# IDC_HD68_Adapter.net
KiCad netlist of a schematic drawn in Altium Designer
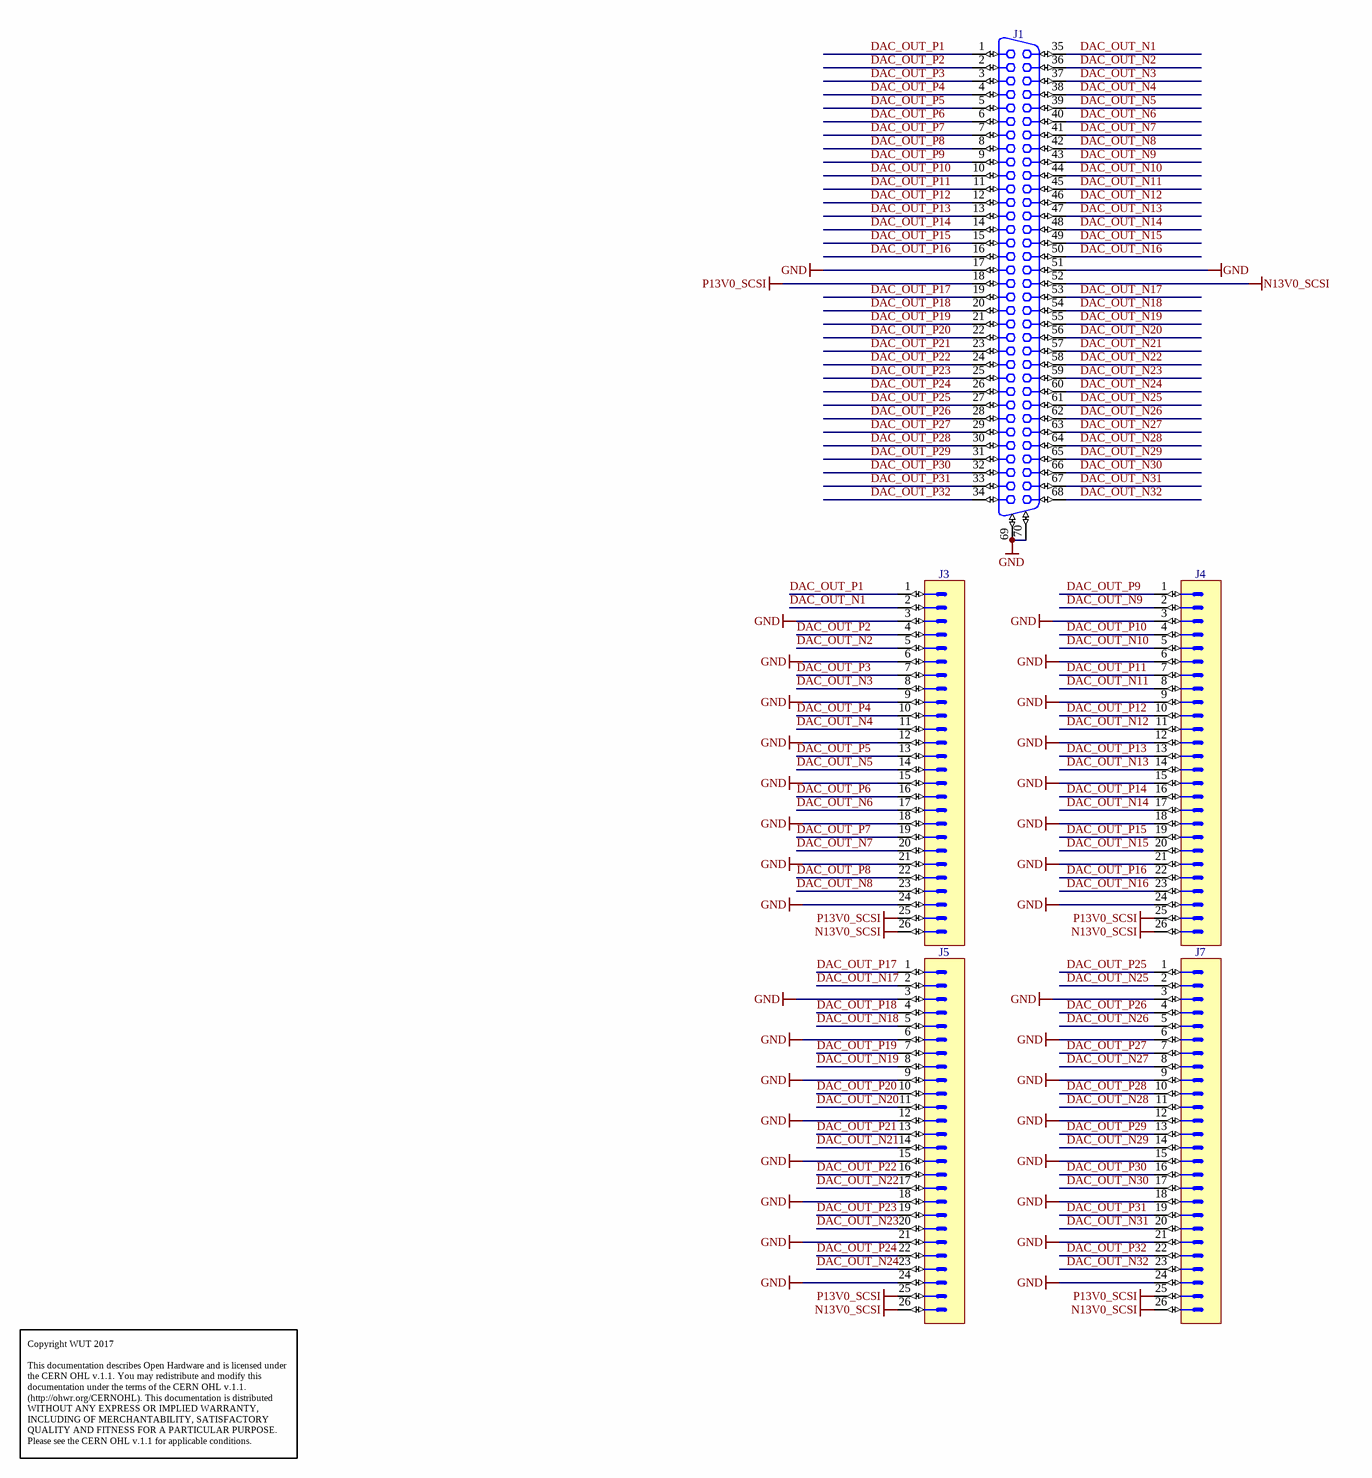
[diagram p0: IDC_HD68_Adapter.SchDoc]

(export (version "E")
  (design (tool "Eeschema 10.0.6"))
  (components
    (comp (ref "J1")
      (value "D-SUB")
      (footprint "TYCO_5787082-7")
      (description "68 contacts, AMPLIMITE .050\", Right Angled Receptacle Series III")
      (fields
        (field (name "PART NUMBER") "TYCO_5787082-7")
        (field (name "MANUFACTURER") "TYCO ELECTRONICS")
        (field (name "AUTHOR") "CERN DEM JLC")
      )
      (libsource (lib "Connectors") (part "TYCO_5787082-7"))
    )
    (comp (ref "J3")
      (value "Header 26")
      (footprint "3M_N2526-6002RB")
      (description "Connector 26 Male")
      (fields
        (field (name "PART NUMBER") "3M_N2526-6002RB")
        (field (name "MANUFACTURER") "3M")
        (field (name "AUTHOR") "CERN DEM JLC")
      )
      (libsource (lib "Connectors") (part "Connector 26 Male"))
    )
    (comp (ref "J4")
      (value "Header 26")
      (footprint "3M_N2526-6002RB")
      (description "Connector 26 Male")
      (fields
        (field (name "PART NUMBER") "3M_N2526-6002RB")
        (field (name "MANUFACTURER") "3M")
        (field (name "AUTHOR") "CERN DEM JLC")
      )
      (libsource (lib "Connectors") (part "Connector 26 Male"))
    )
    (comp (ref "J5")
      (value "Header 26")
      (footprint "3M_N2526-6002RB")
      (description "Connector 26 Male")
      (fields
        (field (name "PART NUMBER") "3M_N2526-6002RB")
        (field (name "MANUFACTURER") "3M")
        (field (name "AUTHOR") "CERN DEM JLC")
      )
      (libsource (lib "Connectors") (part "Connector 26 Male"))
    )
    (comp (ref "J7")
      (value "Header 26")
      (footprint "3M_N2526-6002RB")
      (description "Connector 26 Male")
      (fields
        (field (name "PART NUMBER") "3M_N2526-6002RB")
        (field (name "MANUFACTURER") "3M")
        (field (name "AUTHOR") "CERN DEM JLC")
      )
      (libsource (lib "Connectors") (part "Connector 26 Male"))
    )
  )
  (nets
    (net (code "1") (name "/DAC_OUT_N1") (class "Default")
      (node (ref "J1") (pin "35") (pinfunction "35_35") (pintype "bidirectional"))
      (node (ref "J3") (pin "2") (pinfunction "2_2") (pintype "bidirectional"))
    )
    (net (code "2") (name "/DAC_OUT_N2") (class "Default")
      (node (ref "J1") (pin "36") (pinfunction "36_36") (pintype "bidirectional"))
      (node (ref "J3") (pin "5") (pinfunction "5_5") (pintype "bidirectional"))
    )
    (net (code "3") (name "/DAC_OUT_N3") (class "Default")
      (node (ref "J1") (pin "37") (pinfunction "37_37") (pintype "bidirectional"))
      (node (ref "J3") (pin "8") (pinfunction "8_8") (pintype "bidirectional"))
    )
    (net (code "4") (name "/DAC_OUT_N4") (class "Default")
      (node (ref "J1") (pin "38") (pinfunction "38_38") (pintype "bidirectional"))
      (node (ref "J3") (pin "11") (pinfunction "11_11") (pintype "bidirectional"))
    )
    (net (code "5") (name "/DAC_OUT_N5") (class "Default")
      (node (ref "J1") (pin "39") (pinfunction "39_39") (pintype "bidirectional"))
      (node (ref "J3") (pin "14") (pinfunction "14_14") (pintype "bidirectional"))
    )
    (net (code "6") (name "/DAC_OUT_N6") (class "Default")
      (node (ref "J1") (pin "40") (pinfunction "40_40") (pintype "bidirectional"))
      (node (ref "J3") (pin "17") (pinfunction "17_17") (pintype "bidirectional"))
    )
    (net (code "7") (name "/DAC_OUT_N7") (class "Default")
      (node (ref "J1") (pin "41") (pinfunction "41_41") (pintype "bidirectional"))
      (node (ref "J3") (pin "20") (pinfunction "20_20") (pintype "bidirectional"))
    )
    (net (code "8") (name "/DAC_OUT_N8") (class "Default")
      (node (ref "J1") (pin "42") (pinfunction "42_42") (pintype "bidirectional"))
      (node (ref "J3") (pin "23") (pinfunction "23_23") (pintype "bidirectional"))
    )
    (net (code "9") (name "/DAC_OUT_N9") (class "Default")
      (node (ref "J1") (pin "43") (pinfunction "43_43") (pintype "bidirectional"))
      (node (ref "J4") (pin "2") (pinfunction "2_2") (pintype "bidirectional"))
    )
    (net (code "10") (name "/DAC_OUT_N10") (class "Default")
      (node (ref "J1") (pin "44") (pinfunction "44_44") (pintype "bidirectional"))
      (node (ref "J4") (pin "5") (pinfunction "5_5") (pintype "bidirectional"))
    )
    (net (code "11") (name "/DAC_OUT_N11") (class "Default")
      (node (ref "J1") (pin "45") (pinfunction "45_45") (pintype "bidirectional"))
      (node (ref "J4") (pin "8") (pinfunction "8_8") (pintype "bidirectional"))
    )
    (net (code "12") (name "/DAC_OUT_N12") (class "Default")
      (node (ref "J1") (pin "46") (pinfunction "46_46") (pintype "bidirectional"))
      (node (ref "J4") (pin "11") (pinfunction "11_11") (pintype "bidirectional"))
    )
    (net (code "13") (name "/DAC_OUT_N13") (class "Default")
      (node (ref "J1") (pin "47") (pinfunction "47_47") (pintype "bidirectional"))
      (node (ref "J4") (pin "14") (pinfunction "14_14") (pintype "bidirectional"))
    )
    (net (code "14") (name "/DAC_OUT_N14") (class "Default")
      (node (ref "J1") (pin "48") (pinfunction "48_48") (pintype "bidirectional"))
      (node (ref "J4") (pin "17") (pinfunction "17_17") (pintype "bidirectional"))
    )
    (net (code "15") (name "/DAC_OUT_N15") (class "Default")
      (node (ref "J1") (pin "49") (pinfunction "49_49") (pintype "bidirectional"))
      (node (ref "J4") (pin "20") (pinfunction "20_20") (pintype "bidirectional"))
    )
    (net (code "16") (name "/DAC_OUT_N16") (class "Default")
      (node (ref "J1") (pin "50") (pinfunction "50_50") (pintype "bidirectional"))
      (node (ref "J4") (pin "23") (pinfunction "23_23") (pintype "bidirectional"))
    )
    (net (code "17") (name "/DAC_OUT_N17") (class "Default")
      (node (ref "J1") (pin "53") (pinfunction "53_53") (pintype "bidirectional"))
      (node (ref "J5") (pin "2") (pinfunction "2_2") (pintype "bidirectional"))
    )
    (net (code "18") (name "/DAC_OUT_N18") (class "Default")
      (node (ref "J1") (pin "54") (pinfunction "54_54") (pintype "bidirectional"))
      (node (ref "J5") (pin "5") (pinfunction "5_5") (pintype "bidirectional"))
    )
    (net (code "19") (name "/DAC_OUT_N19") (class "Default")
      (node (ref "J1") (pin "55") (pinfunction "55_55") (pintype "bidirectional"))
      (node (ref "J5") (pin "8") (pinfunction "8_8") (pintype "bidirectional"))
    )
    (net (code "20") (name "/DAC_OUT_N20") (class "Default")
      (node (ref "J1") (pin "56") (pinfunction "56_56") (pintype "bidirectional"))
      (node (ref "J5") (pin "11") (pinfunction "11_11") (pintype "bidirectional"))
    )
    (net (code "21") (name "/DAC_OUT_N21") (class "Default")
      (node (ref "J1") (pin "57") (pinfunction "57_57") (pintype "bidirectional"))
      (node (ref "J5") (pin "14") (pinfunction "14_14") (pintype "bidirectional"))
    )
    (net (code "22") (name "/DAC_OUT_N22") (class "Default")
      (node (ref "J1") (pin "58") (pinfunction "58_58") (pintype "bidirectional"))
      (node (ref "J5") (pin "17") (pinfunction "17_17") (pintype "bidirectional"))
    )
    (net (code "23") (name "/DAC_OUT_N23") (class "Default")
      (node (ref "J1") (pin "59") (pinfunction "59_59") (pintype "bidirectional"))
      (node (ref "J5") (pin "20") (pinfunction "20_20") (pintype "bidirectional"))
    )
    (net (code "24") (name "/DAC_OUT_N24") (class "Default")
      (node (ref "J1") (pin "60") (pinfunction "60_60") (pintype "bidirectional"))
      (node (ref "J5") (pin "23") (pinfunction "23_23") (pintype "bidirectional"))
    )
    (net (code "25") (name "/DAC_OUT_N25") (class "Default")
      (node (ref "J1") (pin "61") (pinfunction "61_61") (pintype "bidirectional"))
      (node (ref "J7") (pin "2") (pinfunction "2_2") (pintype "bidirectional"))
    )
    (net (code "26") (name "/DAC_OUT_N26") (class "Default")
      (node (ref "J1") (pin "62") (pinfunction "62_62") (pintype "bidirectional"))
      (node (ref "J7") (pin "5") (pinfunction "5_5") (pintype "bidirectional"))
    )
    (net (code "27") (name "/DAC_OUT_N27") (class "Default")
      (node (ref "J1") (pin "63") (pinfunction "63_63") (pintype "bidirectional"))
      (node (ref "J7") (pin "8") (pinfunction "8_8") (pintype "bidirectional"))
    )
    (net (code "28") (name "/DAC_OUT_N28") (class "Default")
      (node (ref "J1") (pin "64") (pinfunction "64_64") (pintype "bidirectional"))
      (node (ref "J7") (pin "11") (pinfunction "11_11") (pintype "bidirectional"))
    )
    (net (code "29") (name "/DAC_OUT_N29") (class "Default")
      (node (ref "J1") (pin "65") (pinfunction "65_65") (pintype "bidirectional"))
      (node (ref "J7") (pin "14") (pinfunction "14_14") (pintype "bidirectional"))
    )
    (net (code "30") (name "/DAC_OUT_N30") (class "Default")
      (node (ref "J1") (pin "66") (pinfunction "66_66") (pintype "bidirectional"))
      (node (ref "J7") (pin "17") (pinfunction "17_17") (pintype "bidirectional"))
    )
    (net (code "31") (name "/DAC_OUT_N31") (class "Default")
      (node (ref "J1") (pin "67") (pinfunction "67_67") (pintype "bidirectional"))
      (node (ref "J7") (pin "20") (pinfunction "20_20") (pintype "bidirectional"))
    )
    (net (code "32") (name "/DAC_OUT_N32") (class "Default")
      (node (ref "J1") (pin "68") (pinfunction "68_68") (pintype "bidirectional"))
      (node (ref "J7") (pin "23") (pinfunction "23_23") (pintype "bidirectional"))
    )
    (net (code "33") (name "/DAC_OUT_P1") (class "Default")
      (node (ref "J1") (pin "1") (pinfunction "1_1") (pintype "bidirectional"))
      (node (ref "J3") (pin "1") (pinfunction "1_1") (pintype "bidirectional"))
    )
    (net (code "34") (name "/DAC_OUT_P2") (class "Default")
      (node (ref "J1") (pin "2") (pinfunction "2_2") (pintype "bidirectional"))
      (node (ref "J3") (pin "4") (pinfunction "4_4") (pintype "bidirectional"))
    )
    (net (code "35") (name "/DAC_OUT_P3") (class "Default")
      (node (ref "J1") (pin "3") (pinfunction "3_3") (pintype "bidirectional"))
      (node (ref "J3") (pin "7") (pinfunction "7_7") (pintype "bidirectional"))
    )
    (net (code "36") (name "/DAC_OUT_P4") (class "Default")
      (node (ref "J1") (pin "4") (pinfunction "4_4") (pintype "bidirectional"))
      (node (ref "J3") (pin "10") (pinfunction "10_10") (pintype "bidirectional"))
    )
    (net (code "37") (name "/DAC_OUT_P5") (class "Default")
      (node (ref "J1") (pin "5") (pinfunction "5_5") (pintype "bidirectional"))
      (node (ref "J3") (pin "13") (pinfunction "13_13") (pintype "bidirectional"))
    )
    (net (code "38") (name "/DAC_OUT_P6") (class "Default")
      (node (ref "J1") (pin "6") (pinfunction "6_6") (pintype "bidirectional"))
      (node (ref "J3") (pin "16") (pinfunction "16_16") (pintype "bidirectional"))
    )
    (net (code "39") (name "/DAC_OUT_P7") (class "Default")
      (node (ref "J1") (pin "7") (pinfunction "7_7") (pintype "bidirectional"))
      (node (ref "J3") (pin "19") (pinfunction "19_19") (pintype "bidirectional"))
    )
    (net (code "40") (name "/DAC_OUT_P8") (class "Default")
      (node (ref "J1") (pin "8") (pinfunction "8_8") (pintype "bidirectional"))
      (node (ref "J3") (pin "22") (pinfunction "22_22") (pintype "bidirectional"))
    )
    (net (code "41") (name "/DAC_OUT_P9") (class "Default")
      (node (ref "J1") (pin "9") (pinfunction "9_9") (pintype "bidirectional"))
      (node (ref "J4") (pin "1") (pinfunction "1_1") (pintype "bidirectional"))
    )
    (net (code "42") (name "/DAC_OUT_P10") (class "Default")
      (node (ref "J1") (pin "10") (pinfunction "10_10") (pintype "bidirectional"))
      (node (ref "J4") (pin "4") (pinfunction "4_4") (pintype "bidirectional"))
    )
    (net (code "43") (name "/DAC_OUT_P11") (class "Default")
      (node (ref "J1") (pin "11") (pinfunction "11_11") (pintype "bidirectional"))
      (node (ref "J4") (pin "7") (pinfunction "7_7") (pintype "bidirectional"))
    )
    (net (code "44") (name "/DAC_OUT_P12") (class "Default")
      (node (ref "J1") (pin "12") (pinfunction "12_12") (pintype "bidirectional"))
      (node (ref "J4") (pin "10") (pinfunction "10_10") (pintype "bidirectional"))
    )
    (net (code "45") (name "/DAC_OUT_P13") (class "Default")
      (node (ref "J1") (pin "13") (pinfunction "13_13") (pintype "bidirectional"))
      (node (ref "J4") (pin "13") (pinfunction "13_13") (pintype "bidirectional"))
    )
    (net (code "46") (name "/DAC_OUT_P14") (class "Default")
      (node (ref "J1") (pin "14") (pinfunction "14_14") (pintype "bidirectional"))
      (node (ref "J4") (pin "16") (pinfunction "16_16") (pintype "bidirectional"))
    )
    (net (code "47") (name "/DAC_OUT_P15") (class "Default")
      (node (ref "J1") (pin "15") (pinfunction "15_15") (pintype "bidirectional"))
      (node (ref "J4") (pin "19") (pinfunction "19_19") (pintype "bidirectional"))
    )
    (net (code "48") (name "/DAC_OUT_P16") (class "Default")
      (node (ref "J1") (pin "16") (pinfunction "16_16") (pintype "bidirectional"))
      (node (ref "J4") (pin "22") (pinfunction "22_22") (pintype "bidirectional"))
    )
    (net (code "49") (name "/DAC_OUT_P17") (class "Default")
      (node (ref "J1") (pin "19") (pinfunction "19_19") (pintype "bidirectional"))
      (node (ref "J5") (pin "1") (pinfunction "1_1") (pintype "bidirectional"))
    )
    (net (code "50") (name "/DAC_OUT_P18") (class "Default")
      (node (ref "J1") (pin "20") (pinfunction "20_20") (pintype "bidirectional"))
      (node (ref "J5") (pin "4") (pinfunction "4_4") (pintype "bidirectional"))
    )
    (net (code "51") (name "/DAC_OUT_P19") (class "Default")
      (node (ref "J1") (pin "21") (pinfunction "21_21") (pintype "bidirectional"))
      (node (ref "J5") (pin "7") (pinfunction "7_7") (pintype "bidirectional"))
    )
    (net (code "52") (name "/DAC_OUT_P20") (class "Default")
      (node (ref "J1") (pin "22") (pinfunction "22_22") (pintype "bidirectional"))
      (node (ref "J5") (pin "10") (pinfunction "10_10") (pintype "bidirectional"))
    )
    (net (code "53") (name "/DAC_OUT_P21") (class "Default")
      (node (ref "J1") (pin "23") (pinfunction "23_23") (pintype "bidirectional"))
      (node (ref "J5") (pin "13") (pinfunction "13_13") (pintype "bidirectional"))
    )
    (net (code "54") (name "/DAC_OUT_P22") (class "Default")
      (node (ref "J1") (pin "24") (pinfunction "24_24") (pintype "bidirectional"))
      (node (ref "J5") (pin "16") (pinfunction "16_16") (pintype "bidirectional"))
    )
    (net (code "55") (name "/DAC_OUT_P23") (class "Default")
      (node (ref "J1") (pin "25") (pinfunction "25_25") (pintype "bidirectional"))
      (node (ref "J5") (pin "19") (pinfunction "19_19") (pintype "bidirectional"))
    )
    (net (code "56") (name "/DAC_OUT_P24") (class "Default")
      (node (ref "J1") (pin "26") (pinfunction "26_26") (pintype "bidirectional"))
      (node (ref "J5") (pin "22") (pinfunction "22_22") (pintype "bidirectional"))
    )
    (net (code "57") (name "/DAC_OUT_P25") (class "Default")
      (node (ref "J1") (pin "27") (pinfunction "27_27") (pintype "bidirectional"))
      (node (ref "J7") (pin "1") (pinfunction "1_1") (pintype "bidirectional"))
    )
    (net (code "58") (name "/DAC_OUT_P26") (class "Default")
      (node (ref "J1") (pin "28") (pinfunction "28_28") (pintype "bidirectional"))
      (node (ref "J7") (pin "4") (pinfunction "4_4") (pintype "bidirectional"))
    )
    (net (code "59") (name "/DAC_OUT_P27") (class "Default")
      (node (ref "J1") (pin "29") (pinfunction "29_29") (pintype "bidirectional"))
      (node (ref "J7") (pin "7") (pinfunction "7_7") (pintype "bidirectional"))
    )
    (net (code "60") (name "/DAC_OUT_P28") (class "Default")
      (node (ref "J1") (pin "30") (pinfunction "30_30") (pintype "bidirectional"))
      (node (ref "J7") (pin "10") (pinfunction "10_10") (pintype "bidirectional"))
    )
    (net (code "61") (name "/DAC_OUT_P29") (class "Default")
      (node (ref "J1") (pin "31") (pinfunction "31_31") (pintype "bidirectional"))
      (node (ref "J7") (pin "13") (pinfunction "13_13") (pintype "bidirectional"))
    )
    (net (code "62") (name "/DAC_OUT_P30") (class "Default")
      (node (ref "J1") (pin "32") (pinfunction "32_32") (pintype "bidirectional"))
      (node (ref "J7") (pin "16") (pinfunction "16_16") (pintype "bidirectional"))
    )
    (net (code "63") (name "/DAC_OUT_P31") (class "Default")
      (node (ref "J1") (pin "33") (pinfunction "33_33") (pintype "bidirectional"))
      (node (ref "J7") (pin "19") (pinfunction "19_19") (pintype "bidirectional"))
    )
    (net (code "64") (name "/DAC_OUT_P32") (class "Default")
      (node (ref "J1") (pin "34") (pinfunction "34_34") (pintype "bidirectional"))
      (node (ref "J7") (pin "22") (pinfunction "22_22") (pintype "bidirectional"))
    )
    (net (code "65") (name "GND") (class "Default")
      (node (ref "J1") (pin "17") (pinfunction "17_17") (pintype "bidirectional"))
      (node (ref "J1") (pin "51") (pinfunction "51_51") (pintype "bidirectional"))
      (node (ref "J1") (pin "69") (pinfunction "69_69") (pintype "bidirectional"))
      (node (ref "J1") (pin "70") (pinfunction "70_70") (pintype "bidirectional"))
      (node (ref "J3") (pin "12") (pinfunction "12_12") (pintype "bidirectional"))
      (node (ref "J3") (pin "15") (pinfunction "15_15") (pintype "bidirectional"))
      (node (ref "J3") (pin "18") (pinfunction "18_18") (pintype "bidirectional"))
      (node (ref "J3") (pin "21") (pinfunction "21_21") (pintype "bidirectional"))
      (node (ref "J3") (pin "24") (pinfunction "24_24") (pintype "bidirectional"))
      (node (ref "J3") (pin "3") (pinfunction "3_3") (pintype "bidirectional"))
      (node (ref "J3") (pin "6") (pinfunction "6_6") (pintype "bidirectional"))
      (node (ref "J3") (pin "9") (pinfunction "9_9") (pintype "bidirectional"))
      (node (ref "J4") (pin "12") (pinfunction "12_12") (pintype "bidirectional"))
      (node (ref "J4") (pin "15") (pinfunction "15_15") (pintype "bidirectional"))
      (node (ref "J4") (pin "18") (pinfunction "18_18") (pintype "bidirectional"))
      (node (ref "J4") (pin "21") (pinfunction "21_21") (pintype "bidirectional"))
      (node (ref "J4") (pin "24") (pinfunction "24_24") (pintype "bidirectional"))
      (node (ref "J4") (pin "3") (pinfunction "3_3") (pintype "bidirectional"))
      (node (ref "J4") (pin "6") (pinfunction "6_6") (pintype "bidirectional"))
      (node (ref "J4") (pin "9") (pinfunction "9_9") (pintype "bidirectional"))
      (node (ref "J5") (pin "12") (pinfunction "12_12") (pintype "bidirectional"))
      (node (ref "J5") (pin "15") (pinfunction "15_15") (pintype "bidirectional"))
      (node (ref "J5") (pin "18") (pinfunction "18_18") (pintype "bidirectional"))
      (node (ref "J5") (pin "21") (pinfunction "21_21") (pintype "bidirectional"))
      (node (ref "J5") (pin "24") (pinfunction "24_24") (pintype "bidirectional"))
      (node (ref "J5") (pin "3") (pinfunction "3_3") (pintype "bidirectional"))
      (node (ref "J5") (pin "6") (pinfunction "6_6") (pintype "bidirectional"))
      (node (ref "J5") (pin "9") (pinfunction "9_9") (pintype "bidirectional"))
      (node (ref "J7") (pin "12") (pinfunction "12_12") (pintype "bidirectional"))
      (node (ref "J7") (pin "15") (pinfunction "15_15") (pintype "bidirectional"))
      (node (ref "J7") (pin "18") (pinfunction "18_18") (pintype "bidirectional"))
      (node (ref "J7") (pin "21") (pinfunction "21_21") (pintype "bidirectional"))
      (node (ref "J7") (pin "24") (pinfunction "24_24") (pintype "bidirectional"))
      (node (ref "J7") (pin "3") (pinfunction "3_3") (pintype "bidirectional"))
      (node (ref "J7") (pin "6") (pinfunction "6_6") (pintype "bidirectional"))
      (node (ref "J7") (pin "9") (pinfunction "9_9") (pintype "bidirectional"))
    )
    (net (code "66") (name "N13V0_SCSI") (class "Default")
      (node (ref "J1") (pin "52") (pinfunction "52_52") (pintype "bidirectional"))
      (node (ref "J3") (pin "26") (pinfunction "26_26") (pintype "bidirectional"))
      (node (ref "J4") (pin "26") (pinfunction "26_26") (pintype "bidirectional"))
      (node (ref "J5") (pin "26") (pinfunction "26_26") (pintype "bidirectional"))
      (node (ref "J7") (pin "26") (pinfunction "26_26") (pintype "bidirectional"))
    )
    (net (code "67") (name "P13V0_SCSI") (class "Default")
      (node (ref "J1") (pin "18") (pinfunction "18_18") (pintype "bidirectional"))
      (node (ref "J3") (pin "25") (pinfunction "25_25") (pintype "bidirectional"))
      (node (ref "J4") (pin "25") (pinfunction "25_25") (pintype "bidirectional"))
      (node (ref "J5") (pin "25") (pinfunction "25_25") (pintype "bidirectional"))
      (node (ref "J7") (pin "25") (pinfunction "25_25") (pintype "bidirectional"))
    )
  )
)
